# PWR_TPS54623_3v5_3A.net
KiCad netlist of a schematic drawn in Altium Designer
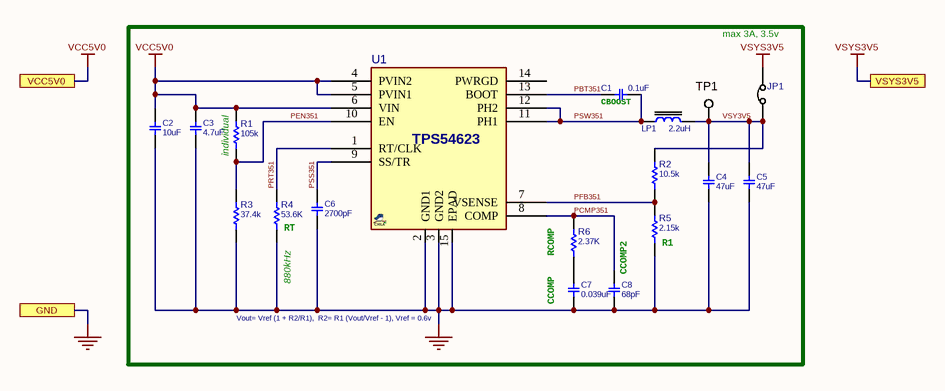
[diagram p0: PWR_TPS54623_3v5_3A.SchDoc]

(export (version "E")
  (design (tool "Eeschema 10.0.6"))
  (components
    (comp (ref "C1")
      (value "0.1uF")
      (footprint "C0402")
      (description "CAP, MLCC, 100nF, 50V, X7R, 10%, 0402C")
      (fields (field (name "MANF") "Murata") (field (name "MANF_P#") "GRM155R61E104"))
      (libsource (lib "passive_mlcc_smd") (part "CAP_SMD_MLCC_100n50V"))
    )
    (comp (ref "C2")
      (value "10uF")
      (footprint "C0402")
      (description "CAP, MLCC")
      (fields (field (name "MANF_P#") "CL05A106MP5NUNC") (field (name "MANF") "Samsung"))
      (libsource (lib "passive_smd") (part "CAP_SMD_MLCC"))
    )
    (comp (ref "C3")
      (value "4.7uF")
      (footprint "C0402")
      (description "CAP, MLCC")
      (fields (field (name "MANF_P#") "CL05A475MP5NRNC") (field (name "MANF") "Samsung"))
      (libsource (lib "passive_smd") (part "CAP_SMD_MLCC"))
    )
    (comp (ref "C4")
      (value "47uF")
      (footprint "C0805")
      (description "CAP, MLCC, X5R 47uF 25V 20% 1206")
      (fields (field (name "MANF") "Samsung") (field (name "MANF_P#") "CL21A476MQYNNNE"))
      (libsource (lib "passive_mlcc_smd") (part "CAP_SMD_MLCC_47u25V"))
    )
    (comp (ref "C5")
      (value "47uF")
      (footprint "C0805")
      (description "CAP, MLCC, X5R 47uF 25V 20% 1206")
      (fields (field (name "MANF") "Samsung") (field (name "MANF_P#") "CL21A476MQYNNNE"))
      (libsource (lib "passive_mlcc_smd") (part "CAP_SMD_MLCC_47u25V"))
    )
    (comp (ref "C6")
      (value "2700pF")
      (footprint "C0402")
      (description "CAP, MLCC, 0402C")
      (libsource (lib "passive_mlcc_smd") (part "CAP_SMD_MLCC_100n50V"))
    )
    (comp (ref "C7")
      (value "0.039uF")
      (footprint "C0402")
      (description "CAP, MLCC, 0402C")
      (libsource (lib "passive_mlcc_smd") (part "CAP_SMD_MLCC_100n50V"))
    )
    (comp (ref "C8")
      (value "68pF")
      (footprint "C0402")
      (description "CAP, MLCC, 0402C")
      (libsource (lib "passive_mlcc_smd") (part "CAP_SMD_MLCC_100n50V"))
    )
    (comp (ref "JP1")
      (value "R0Ohm")
      (footprint "JP_100X60")
      (description "JUMPER, HEADER 2PIN")
      (libsource (lib "test-tp_jumper") (part "JUMPER_HDR_2P"))
    )
    (comp (ref "LP1")
      (value "2.2uH")
      (footprint "L_5")
      (description "INDUCTOR, 3.3uH, 8A (Irms), 10mOhm")
      (fields (field (name "MANF") "Vishay") (field (name "MANF_P#") "IHLP2020CZER2R2M11"))
      (libsource (lib "chila_passive") (part "IND_SMD_2.2uH_4A"))
    )
    (comp (ref "R1")
      (value "105k")
      (footprint "R0402")
      (description "RESISTOR, SMD, 20K, 0402")
      (libsource (lib "chila_passive") (part "RES_SMD"))
    )
    (comp (ref "R2")
      (value "10.5k")
      (footprint "R0402")
      (description "RESISTOR, SMD, 20K, 0402")
      (libsource (lib "chila_passive") (part "RES_SMD"))
    )
    (comp (ref "R3")
      (value "37.4k")
      (footprint "R0402")
      (description "RESISTOR, SMD, 20K, 0402")
      (libsource (lib "chila_passive") (part "RES_SMD"))
    )
    (comp (ref "R4")
      (value "53.6K")
      (footprint "R0402")
      (description "RESISTOR, SMD, 20K, 0402")
      (libsource (lib "chila_passive") (part "RES_SMD"))
    )
    (comp (ref "R5")
      (value "2.15k")
      (footprint "R0402")
      (description "RESISTOR, SMD, 20K, 0402")
      (libsource (lib "chila_passive") (part "RES_SMD"))
    )
    (comp (ref "R6")
      (value "2.37K")
      (footprint "R0402")
      (description "RESISTOR, SMD, 20K, 0402")
      (libsource (lib "chila_passive") (part "RES_SMD"))
    )
    (comp (ref "TP1")
      (value "TESTPOINT_SMD")
      (footprint "TPSMD_S1")
      (description "TEST POINT")
      (fields (field (name "MANF") "MANF") (field (name "MANF_P#") "MANF_P#"))
      (libsource (lib "test-tp_jumper") (part "TESTPOINT_SMD"))
    )
    (comp (ref "U1")
      (value "TPS54623")
      (footprint "QFN50_14T_3535")
      (description "REG, Switching, Buck, 6A, ADJ, 1.6MHz, 4.5~17Vin, VQFN-14")
      (fields (field (name "MANF") "TI") (field (name "MANF_P#") "TPS54623RHL"))
      (libsource (lib "pwr_switching_buck") (part "VREG_TPS54623_VQFN14"))
    )
  )
  (nets
    (net (code "1") (name "/PBT351") (class "Default")
      (node (ref "C1") (pin "1") (pinfunction "1_1") (pintype "passive"))
      (node (ref "U1") (pin "13") (pinfunction "BOOT_13") (pintype "passive"))
    )
    (net (code "2") (name "/PCMP351") (class "Default")
      (node (ref "C8") (pin "1") (pinfunction "1_1") (pintype "passive"))
      (node (ref "R6") (pin "1") (pinfunction "1_1") (pintype "passive"))
      (node (ref "U1") (pin "8") (pinfunction "COMP_8") (pintype "passive"))
    )
    (net (code "3") (name "/PEN351") (class "Default")
      (node (ref "R1") (pin "2") (pinfunction "2_2") (pintype "passive"))
      (node (ref "R3") (pin "1") (pinfunction "1_1") (pintype "passive"))
      (node (ref "U1") (pin "10") (pinfunction "EN_10") (pintype "passive"))
    )
    (net (code "4") (name "/PFB351") (class "Default")
      (node (ref "R2") (pin "2") (pinfunction "2_2") (pintype "passive"))
      (node (ref "R5") (pin "1") (pinfunction "1_1") (pintype "passive"))
      (node (ref "U1") (pin "7") (pinfunction "VSENSE_7") (pintype "passive"))
    )
    (net (code "5") (name "/PRT351") (class "Default")
      (node (ref "R4") (pin "1") (pinfunction "1_1") (pintype "passive"))
      (node (ref "U1") (pin "1") (pinfunction "RT/CLK_1") (pintype "passive"))
    )
    (net (code "6") (name "/PSS351") (class "Default")
      (node (ref "C6") (pin "1") (pinfunction "1_1") (pintype "passive"))
      (node (ref "U1") (pin "9") (pinfunction "SS/TR_9") (pintype "passive"))
    )
    (net (code "7") (name "/PSW351") (class "Default")
      (node (ref "C1") (pin "2") (pinfunction "2_2") (pintype "passive"))
      (node (ref "LP1") (pin "1") (pinfunction "1_1") (pintype "passive"))
      (node (ref "U1") (pin "11") (pinfunction "PH1_11") (pintype "passive"))
      (node (ref "U1") (pin "12") (pinfunction "PH2_12") (pintype "passive"))
    )
    (net (code "8") (name "/VSY3V5") (class "Default")
      (node (ref "C4") (pin "1") (pinfunction "1_1") (pintype "passive"))
      (node (ref "C5") (pin "1") (pinfunction "1_1") (pintype "passive"))
      (node (ref "JP1") (pin "1") (pinfunction "1_1") (pintype "passive"))
      (node (ref "LP1") (pin "2") (pinfunction "2_2") (pintype "passive"))
      (node (ref "R2") (pin "1") (pinfunction "1_1") (pintype "passive"))
      (node (ref "TP1") (pin "1") (pinfunction "1_1") (pintype "passive"))
    )
    (net (code "9") (name "GND") (class "Default")
      (node (ref "C2") (pin "1") (pinfunction "1_1") (pintype "passive"))
      (node (ref "C3") (pin "1") (pinfunction "1_1") (pintype "passive"))
      (node (ref "C4") (pin "2") (pinfunction "2_2") (pintype "passive"))
      (node (ref "C5") (pin "2") (pinfunction "2_2") (pintype "passive"))
      (node (ref "C6") (pin "2") (pinfunction "2_2") (pintype "passive"))
      (node (ref "C7") (pin "2") (pinfunction "2_2") (pintype "passive"))
      (node (ref "C8") (pin "2") (pinfunction "2_2") (pintype "passive"))
      (node (ref "R3") (pin "2") (pinfunction "2_2") (pintype "passive"))
      (node (ref "R4") (pin "2") (pinfunction "2_2") (pintype "passive"))
      (node (ref "R5") (pin "2") (pinfunction "2_2") (pintype "passive"))
      (node (ref "U1") (pin "15") (pinfunction "EPAD_15") (pintype "passive"))
      (node (ref "U1") (pin "2") (pinfunction "GND1_2") (pintype "passive"))
      (node (ref "U1") (pin "3") (pinfunction "GND2_3") (pintype "passive"))
    )
    (net (code "10") (name "Net-(C7-Pad1)") (class "Default")
      (node (ref "C7") (pin "1") (pinfunction "1_1") (pintype "passive"))
      (node (ref "R6") (pin "2") (pinfunction "2_2") (pintype "passive"))
    )
    (net (code "11") (name "VCC5V0") (class "Default")
      (node (ref "C2") (pin "2") (pinfunction "2_2") (pintype "passive"))
      (node (ref "C3") (pin "2") (pinfunction "2_2") (pintype "passive"))
      (node (ref "R1") (pin "1") (pinfunction "1_1") (pintype "passive"))
      (node (ref "U1") (pin "4") (pinfunction "PVIN2_4") (pintype "passive"))
      (node (ref "U1") (pin "5") (pinfunction "PVIN1_5") (pintype "passive"))
      (node (ref "U1") (pin "6") (pinfunction "VIN_6") (pintype "passive"))
    )
    (net (code "12") (name "VSYS3V5") (class "Default")
      (node (ref "JP1") (pin "2") (pinfunction "2_2") (pintype "passive"))
    )
    (net (code "13") (name "unconnected-(U1-PWRGD-Pad14)") (class "Default")
      (node (ref "U1") (pin "14") (pinfunction "PWRGD_14") (pintype "passive"))
    )
  )
)
